# IOandFPGA.net
KiCad netlist of a schematic drawn in Altium Designer
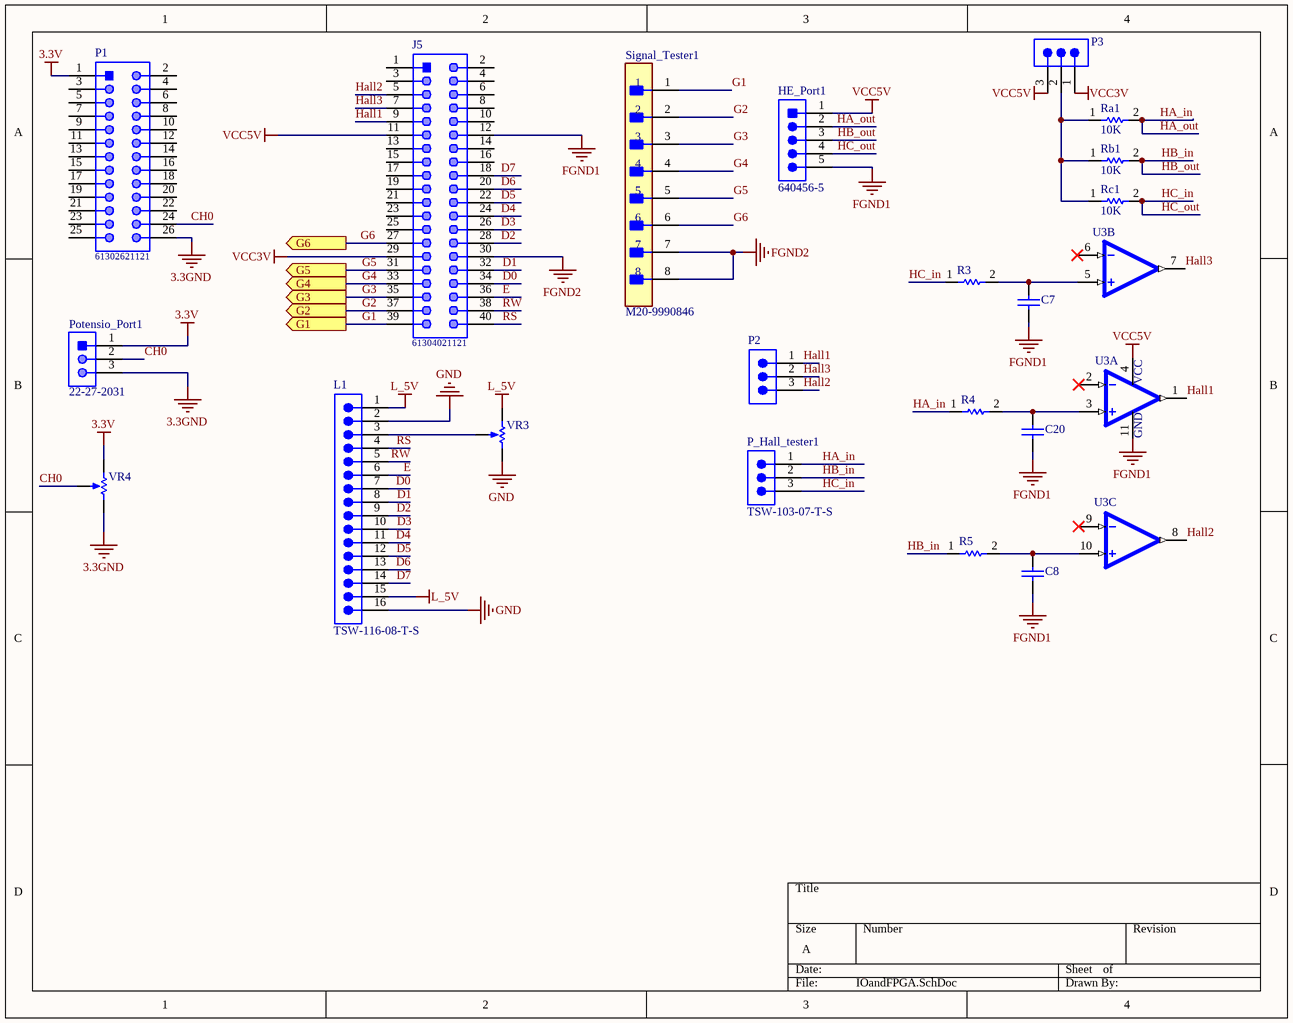
[diagram p0: IOandFPGA.SchDoc]

(export (version "E")
  (design (tool "Eeschema 10.0.6"))
  (components
    (comp (ref "C7")
      (value "0.1µF")
      (footprint "Cap-0.1uf-50V-Ceramic1")
      (description "Lead Capacitor X7R_EIA_ with Capacitance: 0.10F and Rated Voltage: 50Vdc")
      (fields (field (name "MP") "RDER71H104K0K1H03B") (field (name "MF") "Murata"))
      (libsource (lib "YAYAT-LIB") (part "Cap-0.1uf-50V-Ceramic_1"))
    )
    (comp (ref "C8")
      (value "0.1µF")
      (footprint "Cap-0.1uf-50V-Ceramic1")
      (description "Lead Capacitor X7R_EIA_ with Capacitance: 0.10F and Rated Voltage: 50Vdc")
      (fields (field (name "MP") "RDER71H104K0K1H03B") (field (name "MF") "Murata"))
      (libsource (lib "YAYAT-LIB") (part "Cap-0.1uf-50V-Ceramic_1"))
    )
    (comp (ref "C20")
      (value "0.1µF")
      (footprint "Cap-0.1uf-50V-Ceramic1")
      (description "Lead Capacitor X7R_EIA_ with Capacitance: 0.10F and Rated Voltage: 50Vdc")
      (fields (field (name "MP") "RDER71H104K0K1H03B") (field (name "MF") "Murata"))
      (libsource (lib "YAYAT-LIB") (part "Cap-0.1uf-50V-Ceramic_1"))
    )
    (comp (ref "HE_Port1")
      (value "640456-5")
      (footprint "Conn-Wire-header-5pin")
      (fields (field (name "MANUFACTURER") "TE Connectivity"))
      (libsource (lib "YAYAT-LIB") (part "Conn-Wire-header-5pin"))
    )
    (comp (ref "J5")
      (value "61304021121")
      (footprint "Pin-Header-2x20pin")
      (description "THT Vertical Pin Header WR-PHD, Pitch 2.54 mm, Dual Row, 40 pins")
      (fields (field (name "MANUFACTURER") "Wurth Elektronik") (field (name "PUBLISHER") "WurthElektronik"))
      (libsource (lib "YAYAT-LIB") (part "Pin-Header-2x20P"))
    )
    (comp (ref "L1")
      (value "TSW-116-08-T-S")
      (footprint "LCD1602")
      (description "0.025\" SQ Post Header, Through-hole, Vertical, -55 to 105 degC, 2.54 mm Pitch, 16-Pin, Male, RoHS")
      (fields (field (name "MANUFACTURER") "Samtec"))
      (libsource (lib "YAYAT-LIB") (part "LCD1602"))
    )
    (comp (ref "P1")
      (value "61302621121")
      (footprint "DE0-nano")
      (description "THT Vertical Pin Header WR-PHD, Pitch 2.54 mm, Dual Row, 26 pins")
      (fields (field (name "MANUFACTURER") "Wurth Elektronik") (field (name "PUBLISHER") "WurthElektronik"))
      (libsource (lib "YAYAT-LIB") (part "DE0_NANO"))
    )
    (comp (ref "P2")
      (value "TSW-103-07-T-S")
      (footprint "Pin-Header-3pin")
      (description "0.025\" SQ Post Header, Through-hole, Vertical, -55 to 105 degC, 2.54 mm Pitch, 3-Pin, Male, RoHS")
      (fields (field (name "MANUFACTURER") "Samtec"))
      (libsource (lib "YAYAT-LIB") (part "Pin-Header-3pin"))
    )
    (comp (ref "P3")
      (value "TSW-103-07-T-S")
      (footprint "Pin-Header-3pin")
      (description "0.025\" SQ Post Header, Through-hole, Vertical, -55 to 105 degC, 2.54 mm Pitch, 3-Pin, Male, RoHS")
      (fields (field (name "MANUFACTURER") "Samtec"))
      (libsource (lib "YAYAT-LIB") (part "Pin-Header-3pin"))
    )
    (comp (ref "Potensio_Port1")
      (value "22-27-2031")
      (footprint "Conn-Wire-header-3pin")
      (fields (field (name "MANUFACTURER") "Molex"))
      (libsource (lib "YAYAT-LIB") (part "Conn-Wire-header-3pin"))
    )
    (comp (ref "P_Hall_tester1")
      (value "TSW-103-07-T-S")
      (footprint "Pin-Header-3pin")
      (description "0.025\" SQ Post Header, Through-hole, Vertical, -55 to 105 degC, 2.54 mm Pitch, 3-Pin, Male, RoHS")
      (fields (field (name "MANUFACTURER") "Samtec"))
      (libsource (lib "YAYAT-LIB") (part "Pin-Header-3pin"))
    )
    (comp (ref "R3")
      (value "Resistor-1-Watt")
      (footprint "Resistor-1-Watt")
      (description "Resistor")
      (fields
        (field (name "MANUFACTURER_PART_NUMBER") "OK1025E-R52")
        (field (name "MOUSER PART NUMBER") "588-OK1025E-R52")
      )
      (libsource (lib "YAYAT-LIB") (part "Resistor-1-Watt"))
    )
    (comp (ref "R4")
      (value "Resistor-1-Watt")
      (footprint "Resistor-1-Watt")
      (description "Resistor")
      (fields
        (field (name "MANUFACTURER_PART_NUMBER") "OK1025E-R52")
        (field (name "MOUSER PART NUMBER") "588-OK1025E-R52")
      )
      (libsource (lib "YAYAT-LIB") (part "Resistor-1-Watt"))
    )
    (comp (ref "R5")
      (value "Resistor-1-Watt")
      (footprint "Resistor-1-Watt")
      (description "Resistor")
      (fields
        (field (name "MANUFACTURER_PART_NUMBER") "OK1025E-R52")
        (field (name "MOUSER PART NUMBER") "588-OK1025E-R52")
      )
      (libsource (lib "YAYAT-LIB") (part "Resistor-1-Watt"))
    )
    (comp (ref "Ra1")
      (value "10K")
      (footprint "Resistor-1-Watt")
      (description "Resistor")
      (fields
        (field (name "MANUFACTURER_PART_NUMBER") "OK1025E-R52")
        (field (name "MOUSER PART NUMBER") "588-OK1025E-R52")
      )
      (libsource (lib "YAYAT-LIB") (part "Resistor-1-Watt"))
    )
    (comp (ref "Rb1")
      (value "10K")
      (footprint "Resistor-1-Watt")
      (description "Resistor")
      (fields
        (field (name "MANUFACTURER_PART_NUMBER") "OK1025E-R52")
        (field (name "MOUSER PART NUMBER") "588-OK1025E-R52")
      )
      (libsource (lib "YAYAT-LIB") (part "Resistor-1-Watt"))
    )
    (comp (ref "Rc1")
      (value "10K")
      (footprint "Resistor-1-Watt")
      (description "Resistor")
      (fields
        (field (name "MANUFACTURER_PART_NUMBER") "OK1025E-R52")
        (field (name "MOUSER PART NUMBER") "588-OK1025E-R52")
      )
      (libsource (lib "YAYAT-LIB") (part "Resistor-1-Watt"))
    )
    (comp (ref "Signal_Tester1")
      (value "M20-9990846")
      (footprint "Pin-Header-8pin")
      (description "CONN HEADER VERT 8POS 2.54MM")
      (libsource (lib "YAYAT-LIB") (part "Pin-Header-8pin"))
    )
    (comp (ref "U3")
      (value "Op-Amp_LM324")
      (footprint "Op-Amp_LM324")
      (fields (field (name "MP") "LM324NE3"))
      (libsource (lib "YAYAT-LIB") (part "Op-Amp_LM324"))
    )
    (comp (ref "VR3")
      (value "3296W-1-103LF")
      (footprint "Resistor-Trimmer")
      (fields (field (name "TOLERANCE") "1%"))
      (libsource (lib "YAYAT-LIB") (part "Resistor-Trimmer"))
    )
    (comp (ref "VR4")
      (value "3852A-282-103AL")
      (footprint "Potentiometer")
      (description "Diameter Panel Control, 10 KOhm, +/- 10%, 2 W, -1 to 125 degC, 3-Pin THD, RoHS, Bulk")
      (fields (field (name "TOLERANCE") "±10%") (field (name "MANUFACTURER") "Bourns"))
      (libsource (lib "YAYAT-LIB") (part "Potentiometer"))
    )
  )
  (nets
    (net (code "1") (name "/CH0") (class "Default")
      (node (ref "P1") (pin "24") (pinfunction "24_24") (pintype "passive"))
      (node (ref "Potensio_Port1") (pin "2") (pinfunction "2_2") (pintype "passive"))
      (node (ref "VR4") (pin "2") (pinfunction "S_2") (pintype "passive"))
    )
    (net (code "2") (name "/D0") (class "Default")
      (node (ref "J5") (pin "34") (pinfunction "34_34") (pintype "passive"))
      (node (ref "L1") (pin "7") (pinfunction "7_7") (pintype "passive"))
    )
    (net (code "3") (name "/D1") (class "Default")
      (node (ref "J5") (pin "32") (pinfunction "32_32") (pintype "passive"))
      (node (ref "L1") (pin "8") (pinfunction "8_8") (pintype "passive"))
    )
    (net (code "4") (name "/D2") (class "Default")
      (node (ref "J5") (pin "28") (pinfunction "28_28") (pintype "passive"))
      (node (ref "L1") (pin "9") (pinfunction "9_9") (pintype "passive"))
    )
    (net (code "5") (name "/D3") (class "Default")
      (node (ref "J5") (pin "26") (pinfunction "26_26") (pintype "passive"))
      (node (ref "L1") (pin "10") (pinfunction "10_10") (pintype "passive"))
    )
    (net (code "6") (name "/D4") (class "Default")
      (node (ref "J5") (pin "24") (pinfunction "24_24") (pintype "passive"))
      (node (ref "L1") (pin "11") (pinfunction "11_11") (pintype "passive"))
    )
    (net (code "7") (name "/D5") (class "Default")
      (node (ref "J5") (pin "22") (pinfunction "22_22") (pintype "passive"))
      (node (ref "L1") (pin "12") (pinfunction "12_12") (pintype "passive"))
    )
    (net (code "8") (name "/D6") (class "Default")
      (node (ref "J5") (pin "20") (pinfunction "20_20") (pintype "passive"))
      (node (ref "L1") (pin "13") (pinfunction "13_13") (pintype "passive"))
    )
    (net (code "9") (name "/D7") (class "Default")
      (node (ref "J5") (pin "18") (pinfunction "18_18") (pintype "passive"))
      (node (ref "L1") (pin "14") (pinfunction "14_14") (pintype "passive"))
    )
    (net (code "10") (name "/E") (class "Default")
      (node (ref "J5") (pin "36") (pinfunction "36_36") (pintype "passive"))
      (node (ref "L1") (pin "6") (pinfunction "6_6") (pintype "passive"))
    )
    (net (code "11") (name "/G1") (class "Default")
      (node (ref "J5") (pin "39") (pinfunction "39_39") (pintype "passive"))
      (node (ref "Signal_Tester1") (pin "1") (pinfunction "1_1") (pintype "passive"))
    )
    (net (code "12") (name "/G2") (class "Default")
      (node (ref "J5") (pin "37") (pinfunction "37_37") (pintype "passive"))
      (node (ref "Signal_Tester1") (pin "2") (pinfunction "2_2") (pintype "passive"))
    )
    (net (code "13") (name "/G3") (class "Default")
      (node (ref "J5") (pin "35") (pinfunction "35_35") (pintype "passive"))
      (node (ref "Signal_Tester1") (pin "3") (pinfunction "3_3") (pintype "passive"))
    )
    (net (code "14") (name "/G4") (class "Default")
      (node (ref "J5") (pin "33") (pinfunction "33_33") (pintype "passive"))
      (node (ref "Signal_Tester1") (pin "4") (pinfunction "4_4") (pintype "passive"))
    )
    (net (code "15") (name "/G5") (class "Default")
      (node (ref "J5") (pin "31") (pinfunction "31_31") (pintype "passive"))
      (node (ref "Signal_Tester1") (pin "5") (pinfunction "5_5") (pintype "passive"))
    )
    (net (code "16") (name "/G6") (class "Default")
      (node (ref "J5") (pin "27") (pinfunction "27_27") (pintype "passive"))
      (node (ref "Signal_Tester1") (pin "6") (pinfunction "6_6") (pintype "passive"))
    )
    (net (code "17") (name "/HA_in") (class "Default")
      (node (ref "HE_Port1") (pin "2") (pinfunction "RXI_2") (pintype "passive"))
      (node (ref "P_Hall_tester1") (pin "1") (pinfunction "1_1") (pintype "passive"))
      (node (ref "R4") (pin "1") (pinfunction "1_1") (pintype "passive"))
      (node (ref "Ra1") (pin "2") (pinfunction "2_2") (pintype "passive"))
    )
    (net (code "18") (name "/HB_in") (class "Default")
      (node (ref "HE_Port1") (pin "3") (pinfunction "TXO_3") (pintype "passive"))
      (node (ref "P_Hall_tester1") (pin "2") (pinfunction "2_2") (pintype "passive"))
      (node (ref "R5") (pin "1") (pinfunction "1_1") (pintype "passive"))
      (node (ref "Rb1") (pin "2") (pinfunction "2_2") (pintype "passive"))
    )
    (net (code "19") (name "/HC_in") (class "Default")
      (node (ref "HE_Port1") (pin "4") (pinfunction "VCC_4") (pintype "passive"))
      (node (ref "P_Hall_tester1") (pin "3") (pinfunction "3_3") (pintype "passive"))
      (node (ref "R3") (pin "1") (pinfunction "1_1") (pintype "passive"))
      (node (ref "Rc1") (pin "2") (pinfunction "2_2") (pintype "passive"))
    )
    (net (code "20") (name "/Hall1") (class "Default")
      (node (ref "J5") (pin "9") (pinfunction "9_9") (pintype "passive"))
      (node (ref "P2") (pin "1") (pinfunction "1_1") (pintype "passive"))
      (node (ref "U3") (pin "1") (pinfunction "1OUT_1") (pintype "output"))
    )
    (net (code "21") (name "/Hall2") (class "Default")
      (node (ref "J5") (pin "5") (pinfunction "5_5") (pintype "passive"))
      (node (ref "P2") (pin "3") (pinfunction "3_3") (pintype "passive"))
      (node (ref "U3") (pin "8") (pinfunction "3OUT_8") (pintype "output"))
    )
    (net (code "22") (name "/Hall3") (class "Default")
      (node (ref "J5") (pin "7") (pinfunction "7_7") (pintype "passive"))
      (node (ref "P2") (pin "2") (pinfunction "2_2") (pintype "passive"))
      (node (ref "U3") (pin "7") (pinfunction "2OUT_7") (pintype "output"))
    )
    (net (code "23") (name "/RS") (class "Default")
      (node (ref "J5") (pin "40") (pinfunction "40_40") (pintype "passive"))
      (node (ref "L1") (pin "4") (pinfunction "4_4") (pintype "passive"))
    )
    (net (code "24") (name "/RW") (class "Default")
      (node (ref "J5") (pin "38") (pinfunction "38_38") (pintype "passive"))
      (node (ref "L1") (pin "5") (pinfunction "5_5") (pintype "passive"))
    )
    (net (code "25") (name "3.3GND") (class "Default")
      (node (ref "P1") (pin "26") (pinfunction "26_26") (pintype "passive"))
      (node (ref "Potensio_Port1") (pin "3") (pinfunction "3_3") (pintype "passive"))
      (node (ref "VR4") (pin "3") (pinfunction "CW_3") (pintype "passive"))
    )
    (net (code "26") (name "3.3V") (class "Default")
      (node (ref "P1") (pin "1") (pinfunction "1_1") (pintype "passive"))
      (node (ref "Potensio_Port1") (pin "1") (pinfunction "1_1") (pintype "passive"))
      (node (ref "VR4") (pin "1") (pinfunction "CCW_1") (pintype "passive"))
    )
    (net (code "27") (name "FGND1") (class "Default")
      (node (ref "C20") (pin "1") (pinfunction "1_1") (pintype "passive"))
      (node (ref "C7") (pin "1") (pinfunction "1_1") (pintype "passive"))
      (node (ref "C8") (pin "1") (pinfunction "1_1") (pintype "passive"))
      (node (ref "HE_Port1") (pin "5") (pinfunction "CTS_5") (pintype "passive"))
      (node (ref "J5") (pin "12") (pinfunction "12_12") (pintype "passive"))
      (node (ref "U3") (pin "11") (pinfunction "GND_11") (pintype "power_in"))
    )
    (net (code "28") (name "FGND2") (class "Default")
      (node (ref "J5") (pin "30") (pinfunction "30_30") (pintype "passive"))
      (node (ref "Signal_Tester1") (pin "7") (pinfunction "7_7") (pintype "passive"))
      (node (ref "Signal_Tester1") (pin "8") (pinfunction "8_8") (pintype "passive"))
    )
    (net (code "29") (name "GND") (class "Default")
      (node (ref "L1") (pin "16") (pinfunction "16_16") (pintype "passive"))
      (node (ref "L1") (pin "2") (pinfunction "2_2") (pintype "passive"))
      (node (ref "VR3") (pin "3") (pinfunction "CW_3") (pintype "passive"))
    )
    (net (code "30") (name "L_5V") (class "Default")
      (node (ref "L1") (pin "1") (pinfunction "1_1") (pintype "passive"))
      (node (ref "L1") (pin "15") (pinfunction "15_15") (pintype "passive"))
      (node (ref "VR3") (pin "1") (pinfunction "CCW_1") (pintype "passive"))
    )
    (net (code "31") (name "Net-(P3-Pad2)") (class "Default")
      (node (ref "P3") (pin "2") (pinfunction "2_2") (pintype "passive"))
      (node (ref "Ra1") (pin "1") (pinfunction "1_1") (pintype "passive"))
      (node (ref "Rb1") (pin "1") (pinfunction "1_1") (pintype "passive"))
      (node (ref "Rc1") (pin "1") (pinfunction "1_1") (pintype "passive"))
    )
    (net (code "32") (name "Net-(U3A-1IN+)") (class "Default")
      (node (ref "C20") (pin "2") (pinfunction "2_2") (pintype "passive"))
      (node (ref "R4") (pin "2") (pinfunction "2_2") (pintype "passive"))
      (node (ref "U3") (pin "3") (pinfunction "1IN+_3") (pintype "input"))
    )
    (net (code "33") (name "Net-(U3B-2IN+)") (class "Default")
      (node (ref "C7") (pin "2") (pinfunction "2_2") (pintype "passive"))
      (node (ref "R3") (pin "2") (pinfunction "2_2") (pintype "passive"))
      (node (ref "U3") (pin "5") (pinfunction "2IN+_5") (pintype "input"))
    )
    (net (code "34") (name "Net-(U3C-3IN+)") (class "Default")
      (node (ref "C8") (pin "2") (pinfunction "2_2") (pintype "passive"))
      (node (ref "R5") (pin "2") (pinfunction "2_2") (pintype "passive"))
      (node (ref "U3") (pin "10") (pinfunction "3IN+_10") (pintype "input"))
    )
    (net (code "35") (name "Net-(VR3-S)") (class "Default")
      (node (ref "L1") (pin "3") (pinfunction "3_3") (pintype "passive"))
      (node (ref "VR3") (pin "2") (pinfunction "S_2") (pintype "passive"))
    )
    (net (code "36") (name "VCC3V") (class "Default")
      (node (ref "J5") (pin "29") (pinfunction "29_29") (pintype "passive"))
      (node (ref "P3") (pin "1") (pinfunction "1_1") (pintype "passive"))
    )
    (net (code "37") (name "VCC5V") (class "Default")
      (node (ref "HE_Port1") (pin "1") (pinfunction "DTR_1") (pintype "passive"))
      (node (ref "J5") (pin "11") (pinfunction "11_11") (pintype "passive"))
      (node (ref "P3") (pin "3") (pinfunction "3_3") (pintype "passive"))
      (node (ref "U3") (pin "4") (pinfunction "VCC_4") (pintype "power_in"))
    )
    (net (code "38") (name "unconnected-(J5-Pad1)") (class "Default")
      (node (ref "J5") (pin "1") (pinfunction "1_1") (pintype "passive"))
    )
    (net (code "39") (name "unconnected-(J5-Pad2)") (class "Default")
      (node (ref "J5") (pin "2") (pinfunction "2_2") (pintype "passive"))
    )
    (net (code "40") (name "unconnected-(J5-Pad3)") (class "Default")
      (node (ref "J5") (pin "3") (pinfunction "3_3") (pintype "passive"))
    )
    (net (code "41") (name "unconnected-(J5-Pad4)") (class "Default")
      (node (ref "J5") (pin "4") (pinfunction "4_4") (pintype "passive"))
    )
    (net (code "42") (name "unconnected-(J5-Pad6)") (class "Default")
      (node (ref "J5") (pin "6") (pinfunction "6_6") (pintype "passive"))
    )
    (net (code "43") (name "unconnected-(J5-Pad8)") (class "Default")
      (node (ref "J5") (pin "8") (pinfunction "8_8") (pintype "passive"))
    )
    (net (code "44") (name "unconnected-(J5-Pad10)") (class "Default")
      (node (ref "J5") (pin "10") (pinfunction "10_10") (pintype "passive"))
    )
    (net (code "45") (name "unconnected-(J5-Pad13)") (class "Default")
      (node (ref "J5") (pin "13") (pinfunction "13_13") (pintype "passive"))
    )
    (net (code "46") (name "unconnected-(J5-Pad14)") (class "Default")
      (node (ref "J5") (pin "14") (pinfunction "14_14") (pintype "passive"))
    )
    (net (code "47") (name "unconnected-(J5-Pad15)") (class "Default")
      (node (ref "J5") (pin "15") (pinfunction "15_15") (pintype "passive"))
    )
    (net (code "48") (name "unconnected-(J5-Pad16)") (class "Default")
      (node (ref "J5") (pin "16") (pinfunction "16_16") (pintype "passive"))
    )
    (net (code "49") (name "unconnected-(J5-Pad17)") (class "Default")
      (node (ref "J5") (pin "17") (pinfunction "17_17") (pintype "passive"))
    )
    (net (code "50") (name "unconnected-(J5-Pad19)") (class "Default")
      (node (ref "J5") (pin "19") (pinfunction "19_19") (pintype "passive"))
    )
    (net (code "51") (name "unconnected-(J5-Pad21)") (class "Default")
      (node (ref "J5") (pin "21") (pinfunction "21_21") (pintype "passive"))
    )
    (net (code "52") (name "unconnected-(J5-Pad23)") (class "Default")
      (node (ref "J5") (pin "23") (pinfunction "23_23") (pintype "passive"))
    )
    (net (code "53") (name "unconnected-(J5-Pad25)") (class "Default")
      (node (ref "J5") (pin "25") (pinfunction "25_25") (pintype "passive"))
    )
    (net (code "54") (name "unconnected-(P1-Pad2)") (class "Default")
      (node (ref "P1") (pin "2") (pinfunction "2_2") (pintype "passive"))
    )
    (net (code "55") (name "unconnected-(P1-Pad3)") (class "Default")
      (node (ref "P1") (pin "3") (pinfunction "3_3") (pintype "passive"))
    )
    (net (code "56") (name "unconnected-(P1-Pad4)") (class "Default")
      (node (ref "P1") (pin "4") (pinfunction "4_4") (pintype "passive"))
    )
    (net (code "57") (name "unconnected-(P1-Pad5)") (class "Default")
      (node (ref "P1") (pin "5") (pinfunction "5_5") (pintype "passive"))
    )
    (net (code "58") (name "unconnected-(P1-Pad6)") (class "Default")
      (node (ref "P1") (pin "6") (pinfunction "6_6") (pintype "passive"))
    )
    (net (code "59") (name "unconnected-(P1-Pad7)") (class "Default")
      (node (ref "P1") (pin "7") (pinfunction "7_7") (pintype "passive"))
    )
    (net (code "60") (name "unconnected-(P1-Pad8)") (class "Default")
      (node (ref "P1") (pin "8") (pinfunction "8_8") (pintype "passive"))
    )
    (net (code "61") (name "unconnected-(P1-Pad9)") (class "Default")
      (node (ref "P1") (pin "9") (pinfunction "9_9") (pintype "passive"))
    )
    (net (code "62") (name "unconnected-(P1-Pad10)") (class "Default")
      (node (ref "P1") (pin "10") (pinfunction "10_10") (pintype "passive"))
    )
    (net (code "63") (name "unconnected-(P1-Pad11)") (class "Default")
      (node (ref "P1") (pin "11") (pinfunction "11_11") (pintype "passive"))
    )
    (net (code "64") (name "unconnected-(P1-Pad12)") (class "Default")
      (node (ref "P1") (pin "12") (pinfunction "12_12") (pintype "passive"))
    )
    (net (code "65") (name "unconnected-(P1-Pad13)") (class "Default")
      (node (ref "P1") (pin "13") (pinfunction "13_13") (pintype "passive"))
    )
    (net (code "66") (name "unconnected-(P1-Pad14)") (class "Default")
      (node (ref "P1") (pin "14") (pinfunction "14_14") (pintype "passive"))
    )
    (net (code "67") (name "unconnected-(P1-Pad15)") (class "Default")
      (node (ref "P1") (pin "15") (pinfunction "15_15") (pintype "passive"))
    )
    (net (code "68") (name "unconnected-(P1-Pad16)") (class "Default")
      (node (ref "P1") (pin "16") (pinfunction "16_16") (pintype "passive"))
    )
    (net (code "69") (name "unconnected-(P1-Pad17)") (class "Default")
      (node (ref "P1") (pin "17") (pinfunction "17_17") (pintype "passive"))
    )
    (net (code "70") (name "unconnected-(P1-Pad18)") (class "Default")
      (node (ref "P1") (pin "18") (pinfunction "18_18") (pintype "passive"))
    )
    (net (code "71") (name "unconnected-(P1-Pad19)") (class "Default")
      (node (ref "P1") (pin "19") (pinfunction "19_19") (pintype "passive"))
    )
    (net (code "72") (name "unconnected-(P1-Pad20)") (class "Default")
      (node (ref "P1") (pin "20") (pinfunction "20_20") (pintype "passive"))
    )
    (net (code "73") (name "unconnected-(P1-Pad21)") (class "Default")
      (node (ref "P1") (pin "21") (pinfunction "21_21") (pintype "passive"))
    )
    (net (code "74") (name "unconnected-(P1-Pad22)") (class "Default")
      (node (ref "P1") (pin "22") (pinfunction "22_22") (pintype "passive"))
    )
    (net (code "75") (name "unconnected-(P1-Pad23)") (class "Default")
      (node (ref "P1") (pin "23") (pinfunction "23_23") (pintype "passive"))
    )
    (net (code "76") (name "unconnected-(P1-Pad25)") (class "Default")
      (node (ref "P1") (pin "25") (pinfunction "25_25") (pintype "passive"))
    )
    (net (code "77") (name "unconnected-(U3A-1IN--Pad2)") (class "Default")
      (node (ref "U3") (pin "2") (pinfunction "1IN-_2") (pintype "input+no_connect"))
    )
    (net (code "78") (name "unconnected-(U3B-2IN--Pad6)") (class "Default")
      (node (ref "U3") (pin "6") (pinfunction "2IN-_6") (pintype "input+no_connect"))
    )
    (net (code "79") (name "unconnected-(U3C-3IN--Pad9)") (class "Default")
      (node (ref "U3") (pin "9") (pinfunction "3IN-_9") (pintype "input+no_connect"))
    )
  )
)
